# Main.net
KiCad netlist of a schematic drawn in Altium Designer
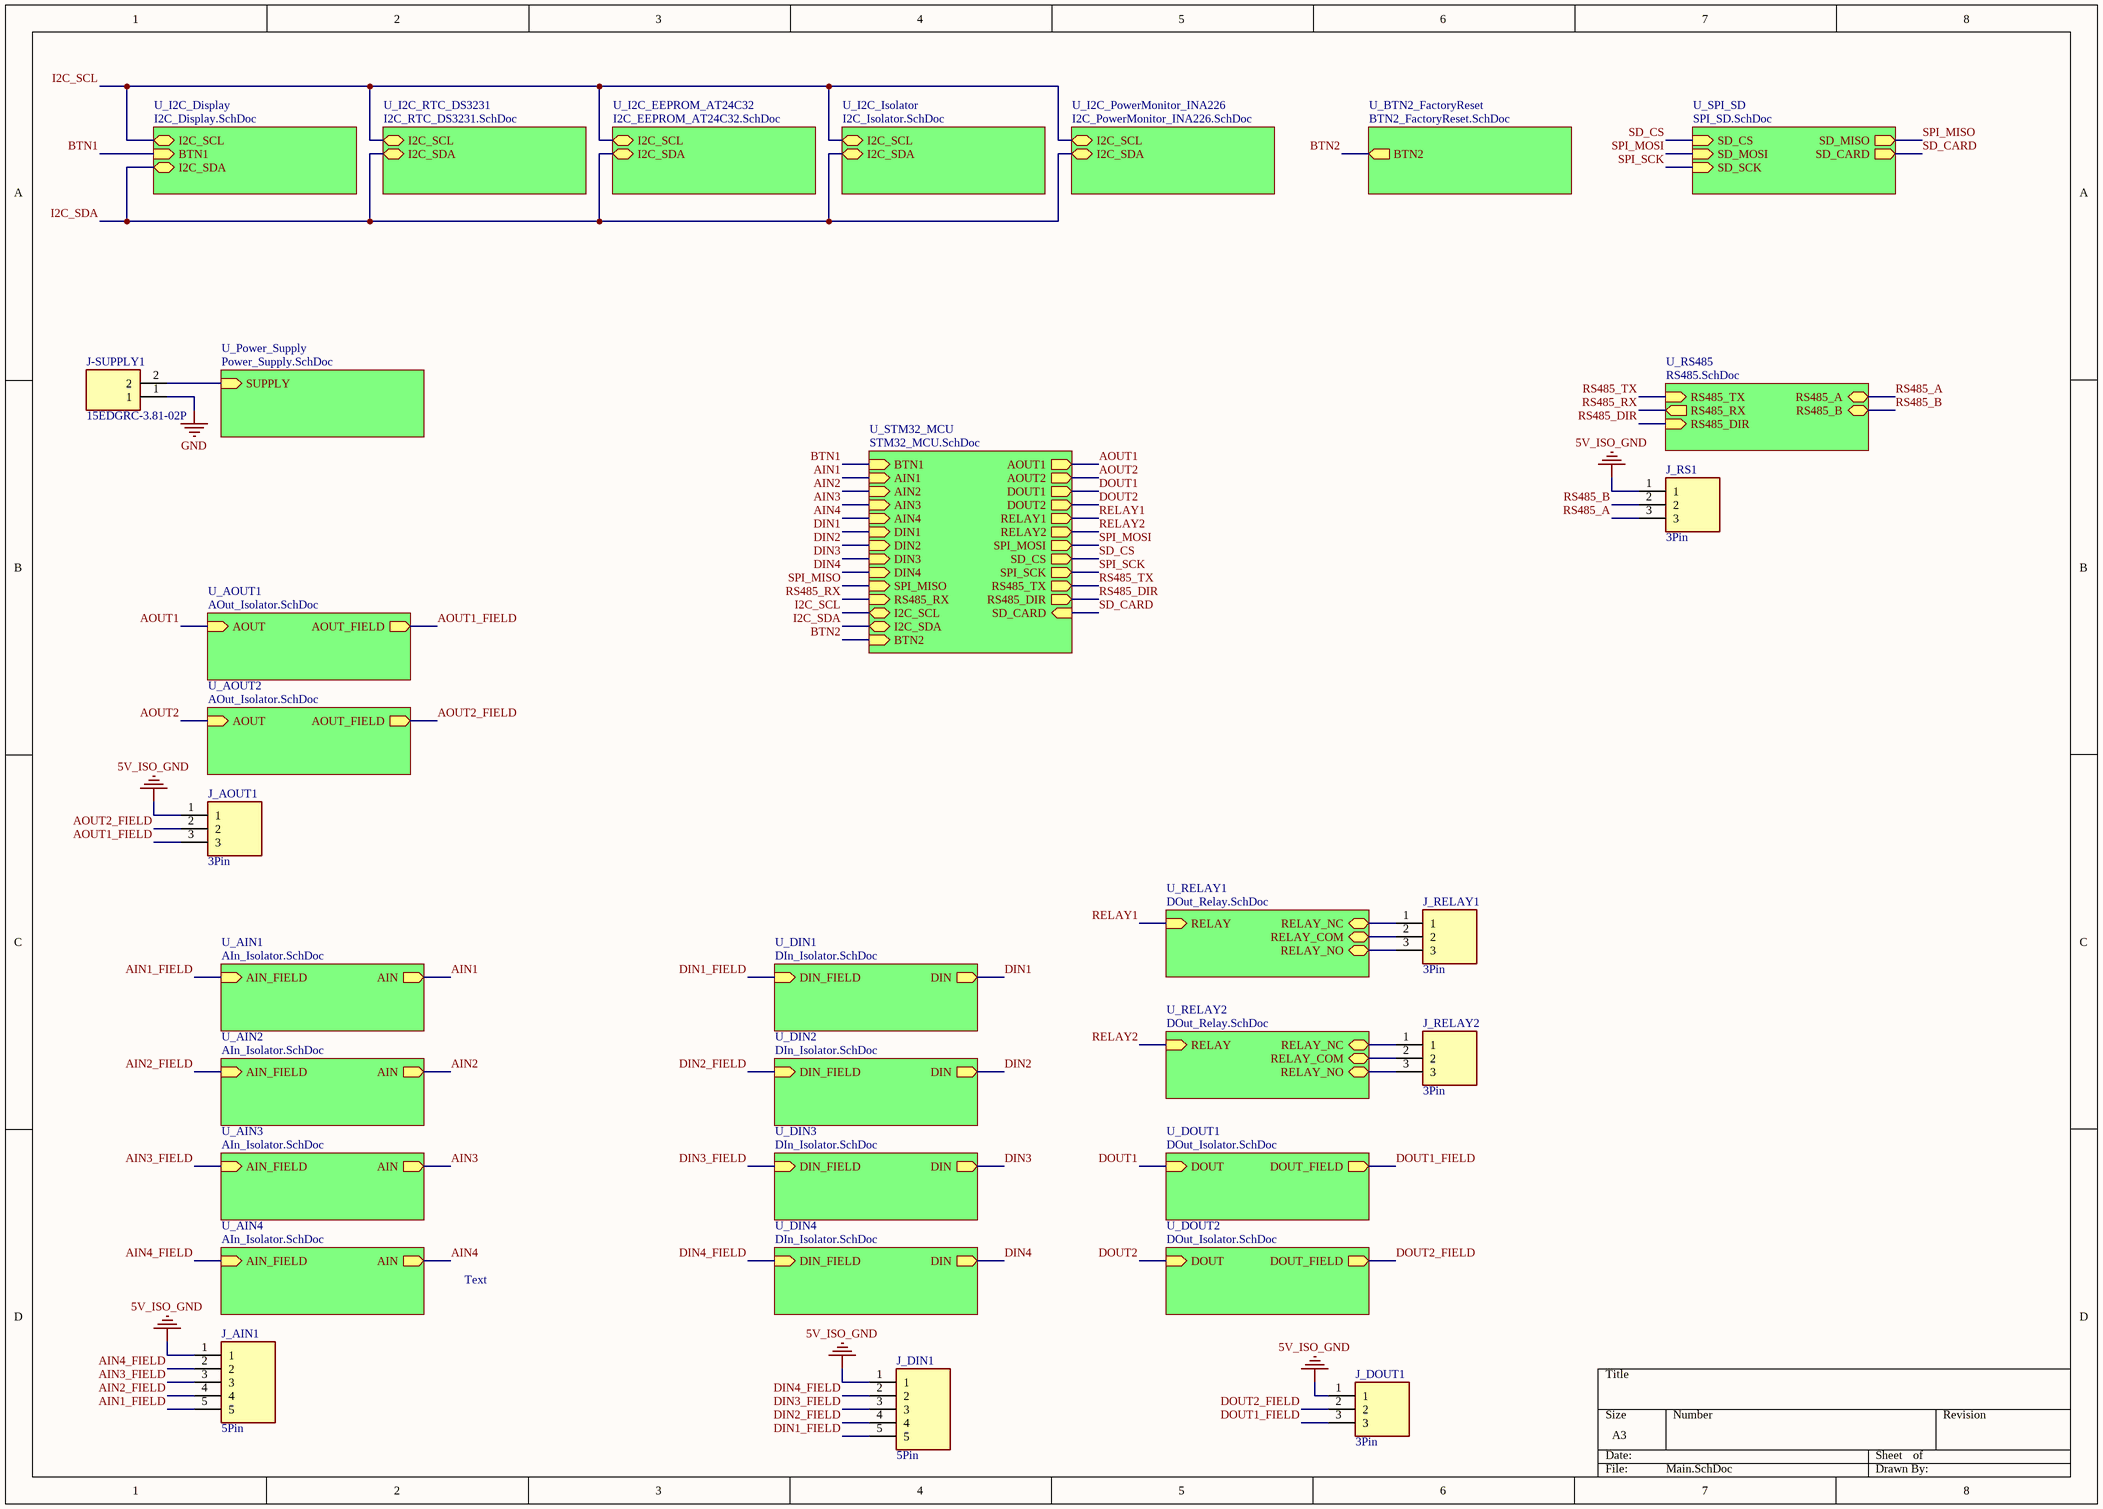
[diagram p0: Main.SchDoc]

(export (version "E")
  (design (tool "Eeschema 10.0.6"))
  (components
    (comp (ref "J-SUPPLY1")
      (value "15EDGRC-3.81-02P")
      (footprint "15EDGRC-3.81-02P")
      (fields (field (name "MANUFACTURER_PART_NUMBER") "15EDGRC-3.81-02P-14-00A(H)"))
      (libsource (lib "15EDGRC-3.81-02P") (part "15EDGRC-3.81-02P"))
    )
    (comp (ref "J_AIN1")
      (value "5Pin")
      (footprint "15EDGRC-3.81-05P:15EDGRC-3.81-05P")
      (fields (field (name "MANUFACTURER_PART_NUMBER") "15EDGRC-3.81-02P-14-00A(H)"))
      (libsource (lib "15EDGRC-3.81-05P") (part "15EDGRC-3.81-05P"))
    )
    (comp (ref "J_AOUT1")
      (value "3Pin")
      (footprint "15EDGRC-3.81-03P")
      (fields (field (name "MANUFACTURER_PART_NUMBER") "15EDGRC-3.81-02P-14-00A(H)"))
      (libsource (lib "15EDGRC-3.81-03P") (part "15EDGRC-3.81-03P"))
    )
    (comp (ref "J_DIN1")
      (value "5Pin")
      (footprint "15EDGRC-3.81-05P:15EDGRC-3.81-05P")
      (fields (field (name "MANUFACTURER_PART_NUMBER") "15EDGRC-3.81-02P-14-00A(H)"))
      (libsource (lib "15EDGRC-3.81-05P") (part "15EDGRC-3.81-05P"))
    )
    (comp (ref "J_DOUT1")
      (value "3Pin")
      (footprint "15EDGRC-3.81-03P")
      (fields (field (name "MANUFACTURER_PART_NUMBER") "15EDGRC-3.81-02P-14-00A(H)"))
      (libsource (lib "15EDGRC-3.81-03P") (part "15EDGRC-3.81-03P"))
    )
    (comp (ref "J_RELAY1")
      (value "3Pin")
      (footprint "15EDGRC-3.81-03P")
      (fields (field (name "MANUFACTURER_PART_NUMBER") "15EDGRC-3.81-02P-14-00A(H)"))
      (libsource (lib "15EDGRC-3.81-03P") (part "15EDGRC-3.81-03P"))
    )
    (comp (ref "J_RELAY2")
      (value "3Pin")
      (footprint "15EDGRC-3.81-03P")
      (fields (field (name "MANUFACTURER_PART_NUMBER") "15EDGRC-3.81-02P-14-00A(H)"))
      (libsource (lib "15EDGRC-3.81-03P") (part "15EDGRC-3.81-03P"))
    )
    (comp (ref "J_RS1")
      (value "3Pin")
      (footprint "15EDGRC-3.81-03P")
      (fields (field (name "MANUFACTURER_PART_NUMBER") "15EDGRC-3.81-02P-14-00A(H)"))
      (libsource (lib "15EDGRC-3.81-03P") (part "15EDGRC-3.81-03P"))
    )
  )
  (nets
    (net (code "2") (name "/AIN1_FIELD") (class "Default")
      (node (ref "J_AIN1") (pin "5") (pinfunction "5_5") (pintype "passive"))
    )
    (net (code "4") (name "/AIN2_FIELD") (class "Default")
      (node (ref "J_AIN1") (pin "4") (pinfunction "4_4") (pintype "passive"))
    )
    (net (code "6") (name "/AIN3_FIELD") (class "Default")
      (node (ref "J_AIN1") (pin "3") (pinfunction "3_3") (pintype "passive"))
    )
    (net (code "8") (name "/AIN4_FIELD") (class "Default")
      (node (ref "J_AIN1") (pin "2") (pinfunction "2_2") (pintype "passive"))
    )
    (net (code "10") (name "/AOUT1_FIELD") (class "Default")
      (node (ref "J_AOUT1") (pin "3") (pinfunction "3_3") (pintype "passive"))
    )
    (net (code "12") (name "/AOUT2_FIELD") (class "Default")
      (node (ref "J_AOUT1") (pin "2") (pinfunction "2_2") (pintype "passive"))
    )
    (net (code "16") (name "/DIN1_FIELD") (class "Default")
      (node (ref "J_DIN1") (pin "5") (pinfunction "5_5") (pintype "passive"))
    )
    (net (code "18") (name "/DIN2_FIELD") (class "Default")
      (node (ref "J_DIN1") (pin "4") (pinfunction "4_4") (pintype "passive"))
    )
    (net (code "20") (name "/DIN3_FIELD") (class "Default")
      (node (ref "J_DIN1") (pin "3") (pinfunction "3_3") (pintype "passive"))
    )
    (net (code "22") (name "/DIN4_FIELD") (class "Default")
      (node (ref "J_DIN1") (pin "2") (pinfunction "2_2") (pintype "passive"))
    )
    (net (code "24") (name "/DOUT1_FIELD") (class "Default")
      (node (ref "J_DOUT1") (pin "3") (pinfunction "3_3") (pintype "passive"))
    )
    (net (code "26") (name "/DOUT2_FIELD") (class "Default")
      (node (ref "J_DOUT1") (pin "2") (pinfunction "2_2") (pintype "passive"))
    )
    (net (code "31") (name "/RELAY_COM") (class "Default")
      (node (ref "J_RELAY2") (pin "2") (pinfunction "2_2") (pintype "passive"))
    )
    (net (code "32") (name "/RELAY_COM_1") (class "Default")
      (node (ref "J_RELAY1") (pin "2") (pinfunction "2_2") (pintype "passive"))
    )
    (net (code "33") (name "/RELAY_NC") (class "Default")
      (node (ref "J_RELAY2") (pin "1") (pinfunction "1_1") (pintype "passive"))
    )
    (net (code "34") (name "/RELAY_NC_1") (class "Default")
      (node (ref "J_RELAY1") (pin "1") (pinfunction "1_1") (pintype "passive"))
    )
    (net (code "35") (name "/RELAY_NO") (class "Default")
      (node (ref "J_RELAY2") (pin "3") (pinfunction "3_3") (pintype "passive"))
    )
    (net (code "36") (name "/RELAY_NO_1") (class "Default")
      (node (ref "J_RELAY1") (pin "3") (pinfunction "3_3") (pintype "passive"))
    )
    (net (code "37") (name "/RS485_A") (class "Default")
      (node (ref "J_RS1") (pin "3") (pinfunction "3_3") (pintype "passive"))
    )
    (net (code "38") (name "/RS485_B") (class "Default")
      (node (ref "J_RS1") (pin "2") (pinfunction "2_2") (pintype "passive"))
    )
    (net (code "47") (name "/SUPPLY") (class "Default")
      (node (ref "J-SUPPLY1") (pin "2") (pinfunction "2_2") (pintype "passive"))
    )
    (net (code "48") (name "5V_ISO_GND") (class "Default")
      (node (ref "J_AIN1") (pin "1") (pinfunction "1_1") (pintype "passive"))
      (node (ref "J_AOUT1") (pin "1") (pinfunction "1_1") (pintype "passive"))
      (node (ref "J_DIN1") (pin "1") (pinfunction "1_1") (pintype "passive"))
      (node (ref "J_DOUT1") (pin "1") (pinfunction "1_1") (pintype "passive"))
      (node (ref "J_RS1") (pin "1") (pinfunction "1_1") (pintype "passive"))
    )
    (net (code "49") (name "GND") (class "Default")
      (node (ref "J-SUPPLY1") (pin "1") (pinfunction "1_1") (pintype "passive"))
    )
  )
)
